# FoxSense_Microcontroller.net
KiCad netlist of a schematic drawn in Altium Designer
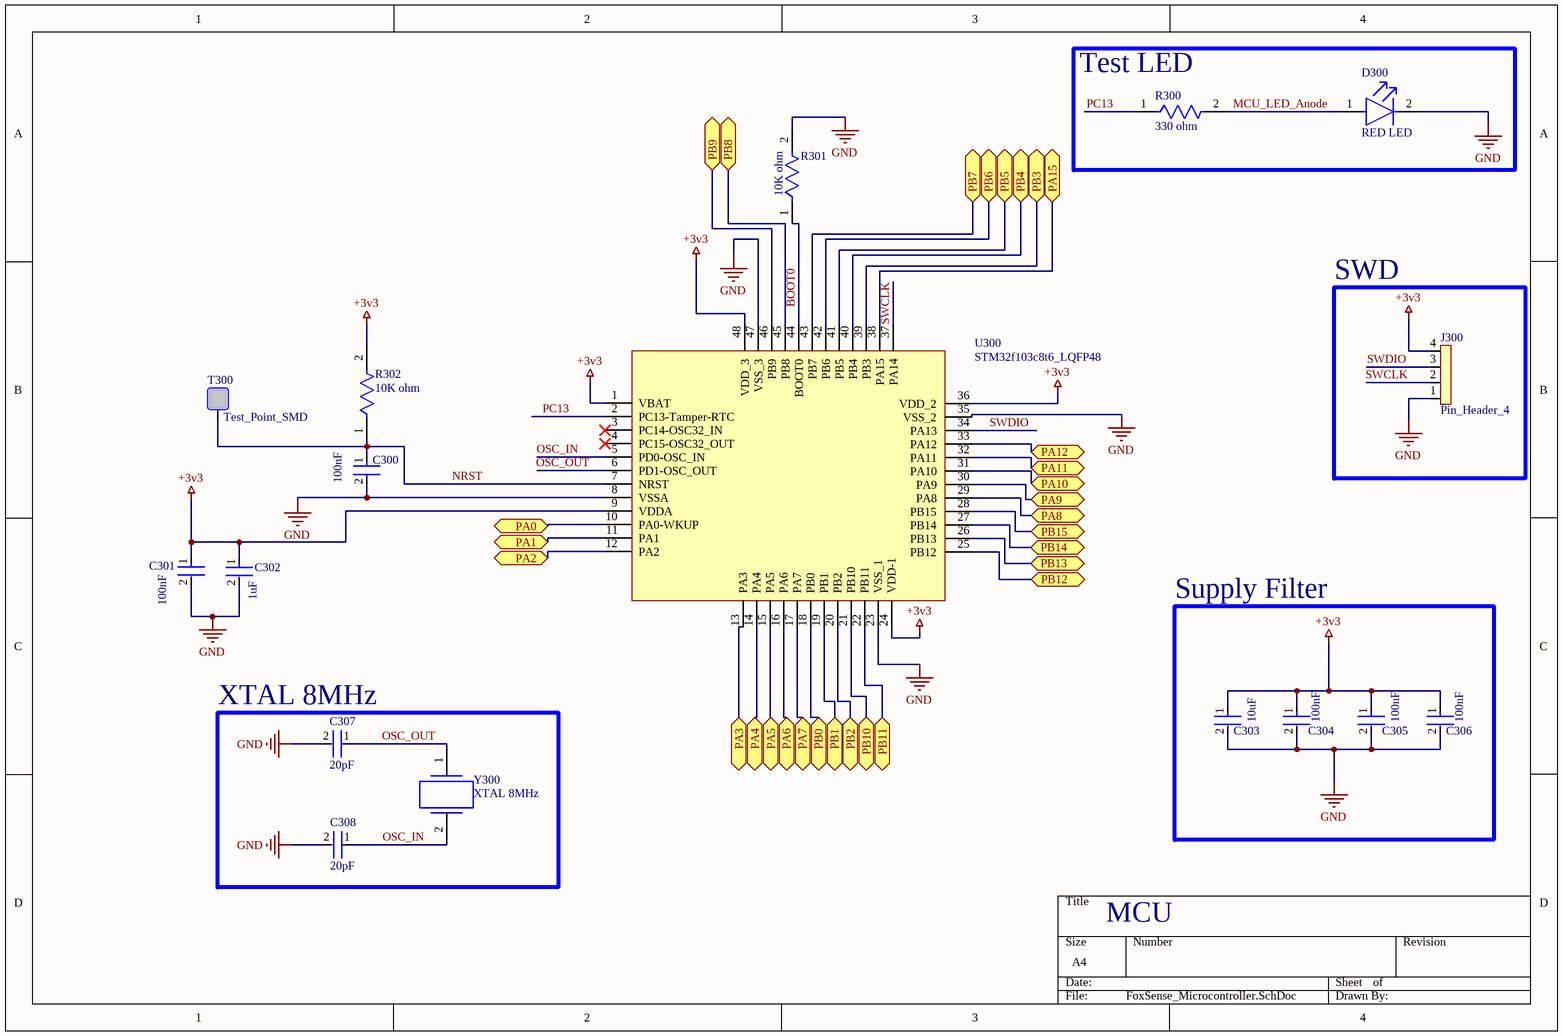
[diagram p0: FoxSense_Microcontroller.SchDoc]

(export (version "E")
  (design (tool "Eeschema 10.0.6"))
  (components
    (comp (ref "C300")
      (value "100nF")
      (footprint "Capacitor_SMD_0805")
      (description "capacitor smd 0805 100nF")
      (libsource (lib "Fox_Schlib") (part "Capacitor_SMD_0805"))
    )
    (comp (ref "C301")
      (value "100nF")
      (footprint "Capacitor_SMD_0805")
      (description "capacitor smd 0805 100nF")
      (libsource (lib "Fox_Schlib") (part "Capacitor_SMD_0805"))
    )
    (comp (ref "C302")
      (value "1uF")
      (footprint "Capacitor_SMD_0805")
      (description "capacitor smd 0805")
      (libsource (lib "Fox_Schlib") (part "Capacitor_SMD_0805"))
    )
    (comp (ref "C303")
      (value "10uF")
      (footprint "Capacitor_SMD_0805")
      (description "capacitor smd 0805 10uF")
      (libsource (lib "Fox_Schlib") (part "Capacitor_SMD_0805"))
    )
    (comp (ref "C304")
      (value "100nF")
      (footprint "Capacitor_SMD_0805")
      (description "capacitor smd 0805 100nF")
      (libsource (lib "Fox_Schlib") (part "Capacitor_SMD_0805"))
    )
    (comp (ref "C305")
      (value "100nF")
      (footprint "Capacitor_SMD_0805")
      (description "capacitor smd 0805 100nF")
      (libsource (lib "Fox_Schlib") (part "Capacitor_SMD_0805"))
    )
    (comp (ref "C306")
      (value "100nF")
      (footprint "Capacitor_SMD_0805")
      (description "capacitor smd 0805 100nF")
      (libsource (lib "Fox_Schlib") (part "Capacitor_SMD_0805"))
    )
    (comp (ref "C307")
      (value "20pF")
      (footprint "Capacitor_SMD_0805")
      (description "capacitor smd 0805 20pF")
      (libsource (lib "Fox_Schlib") (part "Capacitor_SMD_0805"))
    )
    (comp (ref "C308")
      (value "20pF")
      (footprint "Capacitor_SMD_0805")
      (description "capacitor smd 0805 20pF")
      (libsource (lib "Fox_Schlib") (part "Capacitor_SMD_0805"))
    )
    (comp (ref "D300")
      (value "RED LED")
      (footprint "LED_SMD_0805")
      (description "LED SMD 0805")
      (libsource (lib "Fox_Schlib") (part "LED_SMD_0805"))
    )
    (comp (ref "J300")
      (value "Pin_Header_4")
      (footprint "Header4")
      (description "Pin Header 4")
      (libsource (lib "Fox_Schlib") (part "Header4"))
    )
    (comp (ref "R300")
      (value "330 ohm")
      (footprint "Resistor_SMD_0805")
      (description "Resistor SMD 0805 330 ohm")
      (libsource (lib "Fox_Schlib") (part "Resistor_SMD_0805"))
    )
    (comp (ref "R301")
      (value "10K ohm")
      (footprint "Resistor_SMD_0805")
      (description "Resistor SMD 0805 10k ohm")
      (libsource (lib "Fox_Schlib") (part "Resistor_SMD_0805"))
    )
    (comp (ref "R302")
      (value "10K ohm")
      (footprint "Resistor_SMD_0805")
      (description "Resistor SMD 0805 10k ohm")
      (libsource (lib "Fox_Schlib") (part "Resistor_SMD_0805"))
    )
    (comp (ref "T300")
      (value "Test_Point_SMD")
      (footprint "TEST_Point_SMD")
      (description "Test Point SMD")
      (libsource (lib "Fox_Schlib") (part "Test_Point_SMD"))
    )
    (comp (ref "U300")
      (value "STM32f103c8t6_LQFP48")
      (footprint "STM32f103c8t6_LQFP48")
      (description "STM32f103c8t6 LQFP48")
      (libsource (lib "Fox_Schlib") (part "STM32f103c8t6"))
    )
    (comp (ref "Y300")
      (value "XTAL 8MHz")
      (footprint "Crystal_Resonator_SMD_XTAL")
      (description "crystal resonator SMD 8MHz")
      (libsource (lib "Fox_Schlib") (part "Crystal Resonator SMD"))
    )
  )
  (nets
    (net (code "1") (name "+3v3") (class "Default")
      (node (ref "C301") (pin "1") (pinfunction "1_1") (pintype "passive"))
      (node (ref "C302") (pin "1") (pinfunction "1_1") (pintype "passive"))
      (node (ref "C303") (pin "1") (pinfunction "1_1") (pintype "passive"))
      (node (ref "C304") (pin "1") (pinfunction "1_1") (pintype "passive"))
      (node (ref "C305") (pin "1") (pinfunction "1_1") (pintype "passive"))
      (node (ref "C306") (pin "1") (pinfunction "1_1") (pintype "passive"))
      (node (ref "J300") (pin "4") (pinfunction "4_4") (pintype "passive"))
      (node (ref "R302") (pin "2") (pinfunction "2_2") (pintype "passive"))
      (node (ref "U300") (pin "1") (pinfunction "VBAT_1") (pintype "passive"))
      (node (ref "U300") (pin "24") (pinfunction "VDD-1_24") (pintype "passive"))
      (node (ref "U300") (pin "36") (pinfunction "VDD_2_36") (pintype "passive"))
      (node (ref "U300") (pin "48") (pinfunction "VDD_3_48") (pintype "passive"))
      (node (ref "U300") (pin "9") (pinfunction "VDDA_9") (pintype "passive"))
    )
    (net (code "2") (name "/BOOT0") (class "Default")
      (node (ref "R301") (pin "1") (pinfunction "1_1") (pintype "passive"))
      (node (ref "U300") (pin "44") (pinfunction "BOOT0_44") (pintype "passive"))
    )
    (net (code "3") (name "/MCU_LED_Anode") (class "Default")
      (node (ref "D300") (pin "1") (pinfunction "A_1") (pintype "passive"))
      (node (ref "R300") (pin "2") (pinfunction "2_2") (pintype "passive"))
    )
    (net (code "4") (name "/NRST") (class "Default")
      (node (ref "C300") (pin "1") (pinfunction "1_1") (pintype "passive"))
      (node (ref "R302") (pin "1") (pinfunction "1_1") (pintype "passive"))
      (node (ref "T300") (pin "1") (pinfunction "1_1") (pintype "passive"))
      (node (ref "U300") (pin "7") (pinfunction "NRST_7") (pintype "passive"))
    )
    (net (code "5") (name "/OSC_IN") (class "Default")
      (node (ref "C308") (pin "1") (pinfunction "1_1") (pintype "passive"))
      (node (ref "U300") (pin "5") (pinfunction "PD0-OSC_IN_5") (pintype "passive"))
      (node (ref "Y300") (pin "2") (pinfunction "2_2") (pintype "passive"))
    )
    (net (code "6") (name "/OSC_OUT") (class "Default")
      (node (ref "C307") (pin "1") (pinfunction "1_1") (pintype "passive"))
      (node (ref "U300") (pin "6") (pinfunction "PD1-OSC_OUT_6") (pintype "passive"))
      (node (ref "Y300") (pin "1") (pinfunction "1_1") (pintype "passive"))
    )
    (net (code "7") (name "/PA0") (class "Default")
      (node (ref "U300") (pin "10") (pinfunction "PA0-WKUP_10") (pintype "passive"))
    )
    (net (code "8") (name "/PA1") (class "Default")
      (node (ref "U300") (pin "11") (pinfunction "PA1_11") (pintype "passive"))
    )
    (net (code "9") (name "/PA2") (class "Default")
      (node (ref "U300") (pin "12") (pinfunction "PA2_12") (pintype "passive"))
    )
    (net (code "10") (name "/PA3") (class "Default")
      (node (ref "U300") (pin "13") (pinfunction "PA3_13") (pintype "passive"))
    )
    (net (code "11") (name "/PA4") (class "Default")
      (node (ref "U300") (pin "14") (pinfunction "PA4_14") (pintype "passive"))
    )
    (net (code "12") (name "/PA5") (class "Default")
      (node (ref "U300") (pin "15") (pinfunction "PA5_15") (pintype "passive"))
    )
    (net (code "13") (name "/PA6") (class "Default")
      (node (ref "U300") (pin "16") (pinfunction "PA6_16") (pintype "passive"))
    )
    (net (code "14") (name "/PA7") (class "Default")
      (node (ref "U300") (pin "17") (pinfunction "PA7_17") (pintype "passive"))
    )
    (net (code "15") (name "/PA8") (class "Default")
      (node (ref "U300") (pin "29") (pinfunction "PA8_29") (pintype "passive"))
    )
    (net (code "16") (name "/PA9") (class "Default")
      (node (ref "U300") (pin "30") (pinfunction "PA9_30") (pintype "passive"))
    )
    (net (code "17") (name "/PA10") (class "Default")
      (node (ref "U300") (pin "31") (pinfunction "PA10_31") (pintype "passive"))
    )
    (net (code "18") (name "/PA11") (class "Default")
      (node (ref "U300") (pin "32") (pinfunction "PA11_32") (pintype "passive"))
    )
    (net (code "19") (name "/PA12") (class "Default")
      (node (ref "U300") (pin "33") (pinfunction "PA12_33") (pintype "passive"))
    )
    (net (code "20") (name "/PA15") (class "Default")
      (node (ref "U300") (pin "38") (pinfunction "PA15_38") (pintype "passive"))
    )
    (net (code "21") (name "/PB0") (class "Default")
      (node (ref "U300") (pin "18") (pinfunction "PB0_18") (pintype "passive"))
    )
    (net (code "22") (name "/PB1") (class "Default")
      (node (ref "U300") (pin "19") (pinfunction "PB1_19") (pintype "passive"))
    )
    (net (code "23") (name "/PB2") (class "Default")
      (node (ref "U300") (pin "20") (pinfunction "PB2_20") (pintype "passive"))
    )
    (net (code "24") (name "/PB3") (class "Default")
      (node (ref "U300") (pin "39") (pinfunction "PB3_39") (pintype "passive"))
    )
    (net (code "25") (name "/PB4") (class "Default")
      (node (ref "U300") (pin "40") (pinfunction "PB4_40") (pintype "passive"))
    )
    (net (code "26") (name "/PB5") (class "Default")
      (node (ref "U300") (pin "41") (pinfunction "PB5_41") (pintype "passive"))
    )
    (net (code "27") (name "/PB6") (class "Default")
      (node (ref "U300") (pin "42") (pinfunction "PB6_42") (pintype "passive"))
    )
    (net (code "28") (name "/PB7") (class "Default")
      (node (ref "U300") (pin "43") (pinfunction "PB7_43") (pintype "passive"))
    )
    (net (code "29") (name "/PB8") (class "Default")
      (node (ref "U300") (pin "45") (pinfunction "PB8_45") (pintype "passive"))
    )
    (net (code "30") (name "/PB9") (class "Default")
      (node (ref "U300") (pin "46") (pinfunction "PB9_46") (pintype "passive"))
    )
    (net (code "31") (name "/PB10") (class "Default")
      (node (ref "U300") (pin "21") (pinfunction "PB10_21") (pintype "passive"))
    )
    (net (code "32") (name "/PB11") (class "Default")
      (node (ref "U300") (pin "22") (pinfunction "PB11_22") (pintype "passive"))
    )
    (net (code "33") (name "/PB12") (class "Default")
      (node (ref "U300") (pin "25") (pinfunction "PB12_25") (pintype "passive"))
    )
    (net (code "34") (name "/PB13") (class "Default")
      (node (ref "U300") (pin "26") (pinfunction "PB13_26") (pintype "passive"))
    )
    (net (code "35") (name "/PB14") (class "Default")
      (node (ref "U300") (pin "27") (pinfunction "PB14_27") (pintype "passive"))
    )
    (net (code "36") (name "/PB15") (class "Default")
      (node (ref "U300") (pin "28") (pinfunction "PB15_28") (pintype "passive"))
    )
    (net (code "37") (name "/PC13") (class "Default")
      (node (ref "R300") (pin "1") (pinfunction "1_1") (pintype "passive"))
      (node (ref "U300") (pin "2") (pinfunction "PC13-Tamper-RTC_2") (pintype "passive"))
    )
    (net (code "38") (name "/SWCLK") (class "Default")
      (node (ref "J300") (pin "2") (pinfunction "2_2") (pintype "passive"))
      (node (ref "U300") (pin "37") (pinfunction "PA14_37") (pintype "passive"))
    )
    (net (code "39") (name "/SWDIO") (class "Default")
      (node (ref "J300") (pin "3") (pinfunction "3_3") (pintype "passive"))
      (node (ref "U300") (pin "34") (pinfunction "PA13_34") (pintype "passive"))
    )
    (net (code "40") (name "GND") (class "Default")
      (node (ref "C300") (pin "2") (pinfunction "2_2") (pintype "passive"))
      (node (ref "C301") (pin "2") (pinfunction "2_2") (pintype "passive"))
      (node (ref "C302") (pin "2") (pinfunction "2_2") (pintype "passive"))
      (node (ref "C303") (pin "2") (pinfunction "2_2") (pintype "passive"))
      (node (ref "C304") (pin "2") (pinfunction "2_2") (pintype "passive"))
      (node (ref "C305") (pin "2") (pinfunction "2_2") (pintype "passive"))
      (node (ref "C306") (pin "2") (pinfunction "2_2") (pintype "passive"))
      (node (ref "C307") (pin "2") (pinfunction "2_2") (pintype "passive"))
      (node (ref "C308") (pin "2") (pinfunction "2_2") (pintype "passive"))
      (node (ref "D300") (pin "2") (pinfunction "C_2") (pintype "passive"))
      (node (ref "J300") (pin "1") (pinfunction "1_1") (pintype "passive"))
      (node (ref "R301") (pin "2") (pinfunction "2_2") (pintype "passive"))
      (node (ref "U300") (pin "23") (pinfunction "VSS_1_23") (pintype "passive"))
      (node (ref "U300") (pin "35") (pinfunction "VSS_2_35") (pintype "passive"))
      (node (ref "U300") (pin "47") (pinfunction "VSS_3_47") (pintype "passive"))
      (node (ref "U300") (pin "8") (pinfunction "VSSA_8") (pintype "passive"))
    )
    (net (code "41") (name "unconnected-(U300-PC14-OSC32_IN-Pad3)") (class "Default")
      (node (ref "U300") (pin "3") (pinfunction "PC14-OSC32_IN_3") (pintype "passive+no_connect"))
    )
    (net (code "42") (name "unconnected-(U300-PC15-OSC32_OUT-Pad4)") (class "Default")
      (node (ref "U300") (pin "4") (pinfunction "PC15-OSC32_OUT_4") (pintype "passive+no_connect"))
    )
  )
)
